# main.net
KiCad netlist of a schematic drawn in EAGLE
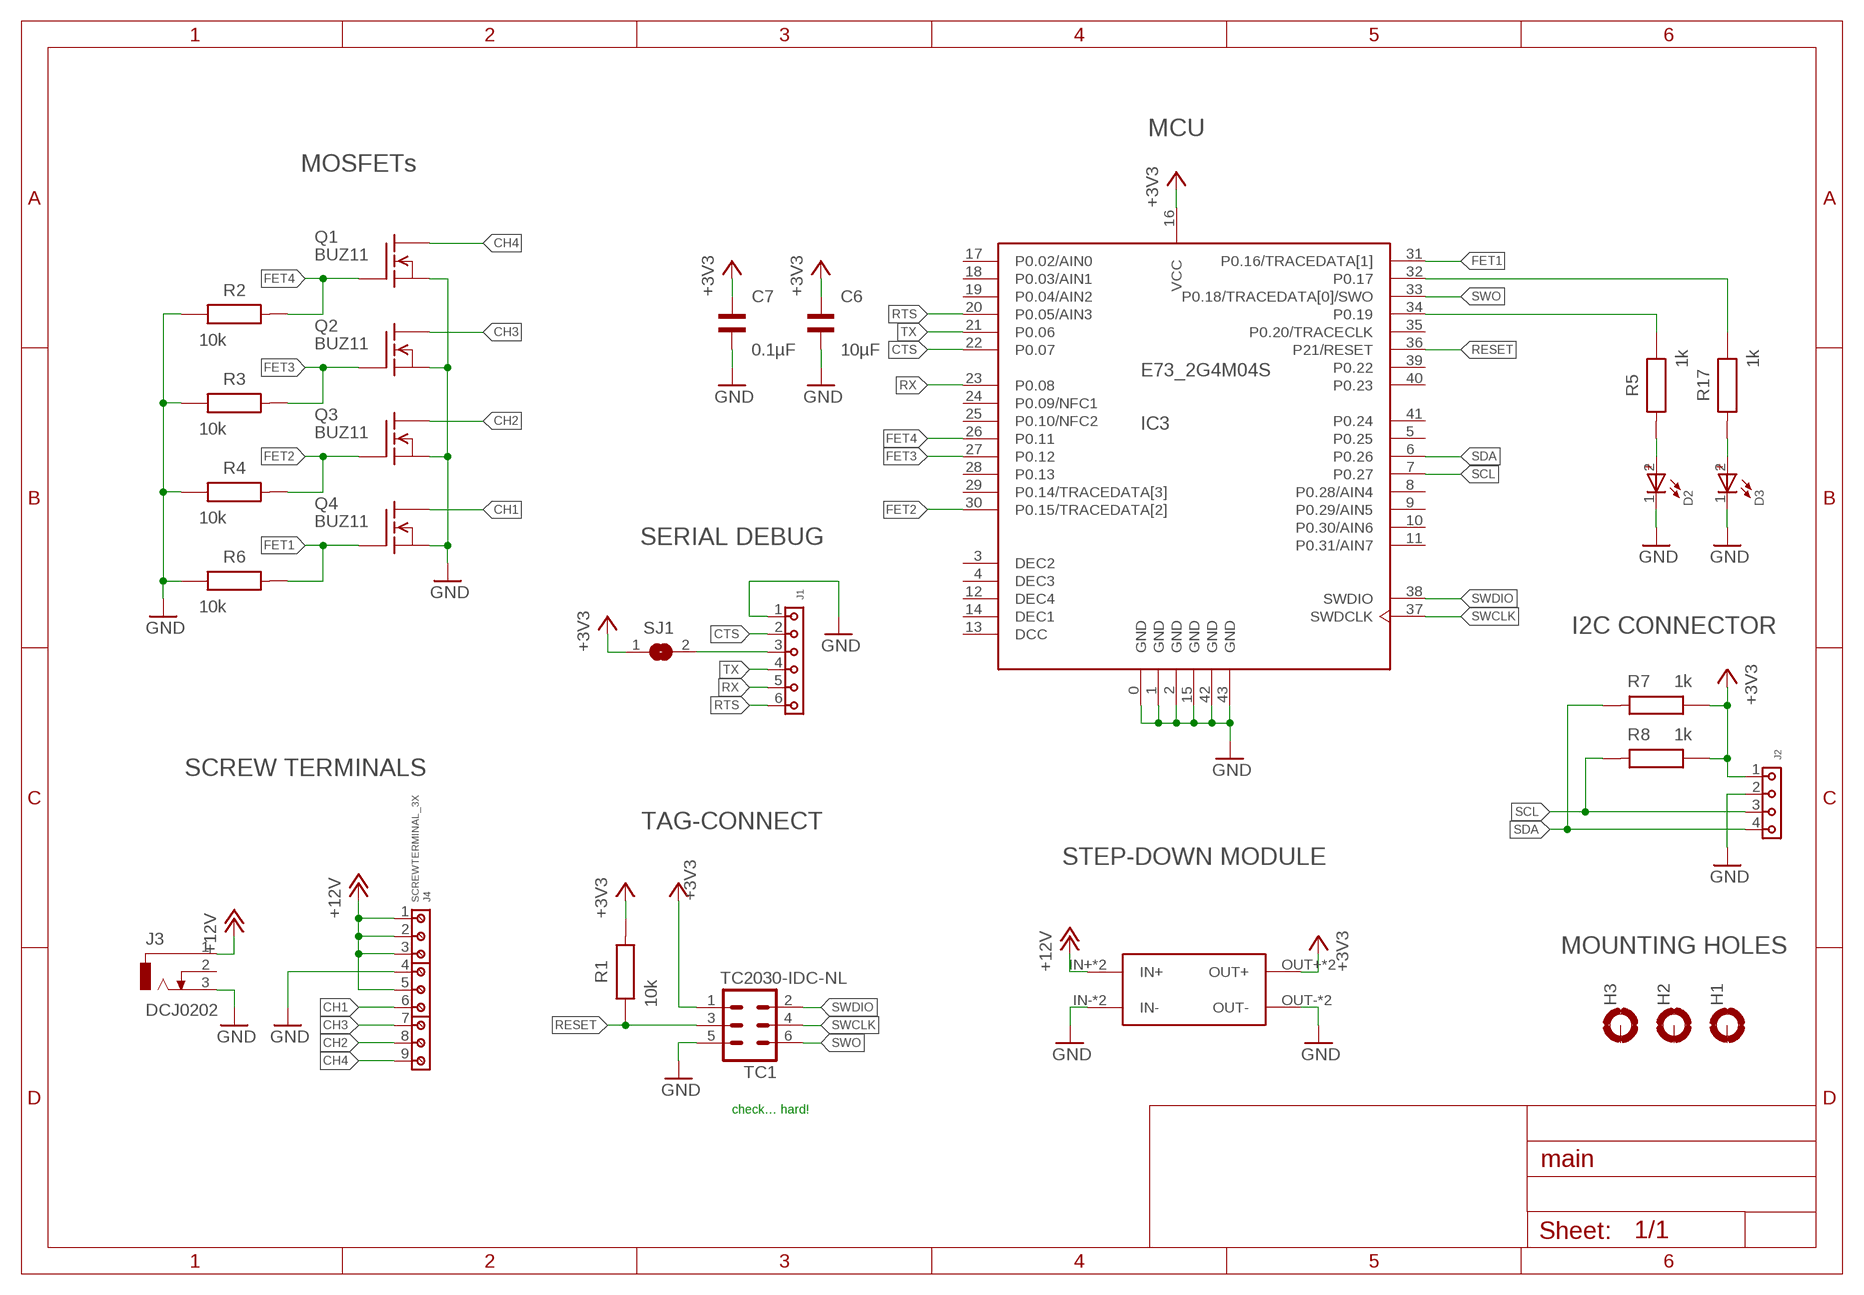
[diagram p0: schematic, sheet 1]

(export (version "E")
  (design (tool "Eeschema 10.0.6"))
  (components
    (comp (ref "C6")
      (value "10µF")
      (footprint "eagle-import:WCAP-CSGP_0603_REFLOW")
      (libsource (lib "eagle-import") (part "WCAP-CSGP_0603_REFLOW_885012206046"))
    )
    (comp (ref "C7")
      (value "0.1µF")
      (footprint "eagle-import:WCAP-CSGP_0603_REFLOW")
      (libsource (lib "eagle-import") (part "WCAP-CSGP_0603_REFLOW_885012206046"))
    )
    (comp (ref "D2")
      (value "WL-SMCW_0603_150060BS75000")
      (footprint "eagle-import:WL-SMCW_0603")
      (libsource (lib "eagle-import") (part "WL-SMCW_0603_150060BS75000"))
    )
    (comp (ref "D3")
      (value "WL-SMCW_0603_150060BS75000")
      (footprint "eagle-import:WL-SMCW_0603")
      (libsource (lib "eagle-import") (part "WL-SMCW_0603_150060BS75000"))
    )
    (comp (ref "H1")
      (value "MOUNT-PAD-ROUND3.2")
      (footprint "eagle-import:3,2-PAD")
      (libsource (lib "eagle-import") (part "MOUNT-PAD-ROUND3.2"))
    )
    (comp (ref "H2")
      (value "MOUNT-PAD-ROUND3.2")
      (footprint "eagle-import:3,2-PAD")
      (libsource (lib "eagle-import") (part "MOUNT-PAD-ROUND3.2"))
    )
    (comp (ref "H3")
      (value "MOUNT-PAD-ROUND3.2")
      (footprint "eagle-import:3,2-PAD")
      (libsource (lib "eagle-import") (part "MOUNT-PAD-ROUND3.2"))
    )
    (comp (ref "IC3")
      (value "E73_2G4M04S")
      (footprint "eagle-import:E73_2G4M04S")
      (libsource (lib "eagle-import") (part "E73_2G4M04S"))
    )
    (comp (ref "J1")
      (value "6130XX11821_61300611821")
      (footprint "eagle-import:61300611821")
      (libsource (lib "eagle-import") (part "6130XX11821_61300611821"))
    )
    (comp (ref "J2")
      (value "6130XX11821_61300411821")
      (footprint "eagle-import:61300411821")
      (libsource (lib "eagle-import") (part "6130XX11821_61300411821"))
    )
    (comp (ref "J3")
      (value "DCJ0202")
      (footprint "eagle-import:DCJ0202")
      (libsource (lib "eagle-import") (part "DCJ0202"))
    )
    (comp (ref "J4")
      (value "SCREWTERMINAL_3X")
      (footprint "eagle-import:691102710003")
      (libsource (lib "eagle-import") (part "SCREWTERMINAL_3X"))
    )
    (comp (ref "Q1")
      (value "BUZ11")
      (footprint "eagle-import:TO220")
      (libsource (lib "eagle-import") (part "BUZ11"))
    )
    (comp (ref "Q2")
      (value "BUZ11")
      (footprint "eagle-import:TO220")
      (libsource (lib "eagle-import") (part "BUZ11"))
    )
    (comp (ref "Q3")
      (value "BUZ11")
      (footprint "eagle-import:TO220")
      (libsource (lib "eagle-import") (part "BUZ11"))
    )
    (comp (ref "Q4")
      (value "BUZ11")
      (footprint "eagle-import:TO220")
      (libsource (lib "eagle-import") (part "BUZ11"))
    )
    (comp (ref "R1")
      (value "10k")
      (footprint "eagle-import:WRIS-PSMB_0603_1.6X0.8X0.35X0.6(LXWXHXPW)")
      (libsource (lib "eagle-import") (part "WRIS-PSMB_0603_1.6X0.8X0.35X0.6_580060716001"))
    )
    (comp (ref "R2")
      (value "10k")
      (footprint "eagle-import:WRIS-PSMB_0603_1.6X0.8X0.35X0.6(LXWXHXPW)")
      (libsource (lib "eagle-import") (part "WRIS-PSMB_0603_1.6X0.8X0.35X0.6_580060716001"))
    )
    (comp (ref "R3")
      (value "10k")
      (footprint "eagle-import:WRIS-PSMB_0603_1.6X0.8X0.35X0.6(LXWXHXPW)")
      (libsource (lib "eagle-import") (part "WRIS-PSMB_0603_1.6X0.8X0.35X0.6_580060716001"))
    )
    (comp (ref "R4")
      (value "10k")
      (footprint "eagle-import:WRIS-PSMB_0603_1.6X0.8X0.35X0.6(LXWXHXPW)")
      (libsource (lib "eagle-import") (part "WRIS-PSMB_0603_1.6X0.8X0.35X0.6_580060716001"))
    )
    (comp (ref "R5")
      (value "1k")
      (footprint "eagle-import:WRIS-PSMB_0603_1.6X0.8X0.35X0.6(LXWXHXPW)")
      (libsource (lib "eagle-import") (part "WRIS-PSMB_0603_1.6X0.8X0.35X0.6_580060716001"))
    )
    (comp (ref "R6")
      (value "10k")
      (footprint "eagle-import:WRIS-PSMB_0603_1.6X0.8X0.35X0.6(LXWXHXPW)")
      (libsource (lib "eagle-import") (part "WRIS-PSMB_0603_1.6X0.8X0.35X0.6_580060716001"))
    )
    (comp (ref "R7")
      (value "1k")
      (footprint "eagle-import:WRIS-PSMB_0603_1.6X0.8X0.35X0.6(LXWXHXPW)")
      (libsource (lib "eagle-import") (part "WRIS-PSMB_0603_1.6X0.8X0.35X0.6_580060716001"))
    )
    (comp (ref "R8")
      (value "1k")
      (footprint "eagle-import:WRIS-PSMB_0603_1.6X0.8X0.35X0.6(LXWXHXPW)")
      (libsource (lib "eagle-import") (part "WRIS-PSMB_0603_1.6X0.8X0.35X0.6_580060716001"))
    )
    (comp (ref "R17")
      (value "1k")
      (footprint "eagle-import:WRIS-PSMB_0603_1.6X0.8X0.35X0.6(LXWXHXPW)")
      (libsource (lib "eagle-import") (part "WRIS-PSMB_0603_1.6X0.8X0.35X0.6_580060716001"))
    )
    (comp (ref "SJ1") (value "SJ") (footprint "eagle-import:SJ") (libsource (lib "eagle-import") (part "SJ")))
    (comp (ref "TC1")
      (value "TC2030-IDC-NL")
      (footprint "eagle-import:TC2030-IDC-NL")
      (libsource (lib "eagle-import") (part "TC2030-IDC-NL"))
    )
    (comp (ref "U$1")
      (value "LM2596-MODULE")
      (footprint "eagle-import:LM2596-MODULE")
      (libsource (lib "eagle-import") (part "LM2596-MODULE"))
    )
  )
  (nets
    (net (code "1") (name "+3V3") (class "Default")
      (node (ref "C6") (pin "2") (pinfunction "2_2") (pintype "passive"))
      (node (ref "C7") (pin "2") (pinfunction "2_2") (pintype "passive"))
      (node (ref "IC3") (pin "16") (pinfunction "VCC_16") (pintype "passive"))
      (node (ref "J2") (pin "1") (pinfunction "1_1") (pintype "passive"))
      (node (ref "R1") (pin "2") (pinfunction "2_2") (pintype "passive"))
      (node (ref "R7") (pin "1") (pinfunction "1_1") (pintype "passive"))
      (node (ref "R8") (pin "1") (pinfunction "1_1") (pintype "passive"))
      (node (ref "SJ1") (pin "1") (pinfunction "1_1") (pintype "passive"))
      (node (ref "TC1") (pin "1") (pinfunction "1_1") (pintype "passive"))
      (node (ref "U$1") (pin "OUT+") (pinfunction "OUT+_OUT+") (pintype "bidirectional"))
      (node (ref "U$1") (pin "OUT+1") (pinfunction "OUT+_OUT+1") (pintype "bidirectional"))
    )
    (net (code "2") (name "+12V") (class "Default")
      (node (ref "J3") (pin "1") (pinfunction "1_1") (pintype "passive"))
      (node (ref "J4") (pin "1") (pinfunction "1_1") (pintype "passive"))
      (node (ref "J4") (pin "2") (pinfunction "2_2") (pintype "passive"))
      (node (ref "J4") (pin "3") (pinfunction "3_3") (pintype "passive"))
      (node (ref "J4") (pin "5") (pinfunction "5_5") (pintype "passive"))
      (node (ref "U$1") (pin "IN+") (pinfunction "IN+_IN+") (pintype "bidirectional"))
      (node (ref "U$1") (pin "IN+1") (pinfunction "IN+_IN+1") (pintype "bidirectional"))
    )
    (net (code "3") (name "/DCC") (class "Default")
      (node (ref "IC3") (pin "13") (pinfunction "DCC_13") (pintype "power_in"))
    )
    (net (code "4") (name "/DEC1") (class "Default")
      (node (ref "IC3") (pin "14") (pinfunction "DEC1_14") (pintype "power_in"))
    )
    (net (code "5") (name "/DEC2") (class "Default")
      (node (ref "IC3") (pin "3") (pinfunction "DEC2_3") (pintype "power_in"))
    )
    (net (code "6") (name "/DEC3") (class "Default")
      (node (ref "IC3") (pin "4") (pinfunction "DEC3_4") (pintype "power_in"))
    )
    (net (code "7") (name "/DEC4") (class "Default")
      (node (ref "IC3") (pin "12") (pinfunction "DEC4_12") (pintype "power_in"))
    )
    (net (code "8") (name "CH1") (class "Default")
      (node (ref "J4") (pin "6") (pinfunction "6_6") (pintype "passive"))
      (node (ref "Q4") (pin "2") (pinfunction "D_2") (pintype "passive"))
    )
    (net (code "9") (name "CH2") (class "Default")
      (node (ref "J4") (pin "8") (pinfunction "8_8") (pintype "passive"))
      (node (ref "Q3") (pin "2") (pinfunction "D_2") (pintype "passive"))
    )
    (net (code "10") (name "CH3") (class "Default")
      (node (ref "J4") (pin "7") (pinfunction "7_7") (pintype "passive"))
      (node (ref "Q2") (pin "2") (pinfunction "D_2") (pintype "passive"))
    )
    (net (code "11") (name "CH4") (class "Default")
      (node (ref "J4") (pin "9") (pinfunction "9_9") (pintype "passive"))
      (node (ref "Q1") (pin "2") (pinfunction "D_2") (pintype "passive"))
    )
    (net (code "12") (name "CTS") (class "Default")
      (node (ref "IC3") (pin "22") (pinfunction "P0.07_22") (pintype "bidirectional"))
      (node (ref "J1") (pin "2") (pinfunction "2_2") (pintype "passive"))
    )
    (net (code "13") (name "FET1") (class "Default")
      (node (ref "IC3") (pin "31") (pinfunction "P0.16/TRACEDATA[1]_31") (pintype "bidirectional"))
      (node (ref "Q4") (pin "1") (pinfunction "G_1") (pintype "passive"))
      (node (ref "R6") (pin "2") (pinfunction "2_2") (pintype "passive"))
    )
    (net (code "14") (name "FET2") (class "Default")
      (node (ref "IC3") (pin "30") (pinfunction "P0.15/TRACEDATA[2]_30") (pintype "bidirectional"))
      (node (ref "Q3") (pin "1") (pinfunction "G_1") (pintype "passive"))
      (node (ref "R4") (pin "2") (pinfunction "2_2") (pintype "passive"))
    )
    (net (code "15") (name "FET3") (class "Default")
      (node (ref "IC3") (pin "27") (pinfunction "P0.12_27") (pintype "bidirectional"))
      (node (ref "Q2") (pin "1") (pinfunction "G_1") (pintype "passive"))
      (node (ref "R3") (pin "2") (pinfunction "2_2") (pintype "passive"))
    )
    (net (code "16") (name "FET4") (class "Default")
      (node (ref "IC3") (pin "26") (pinfunction "P0.11_26") (pintype "bidirectional"))
      (node (ref "Q1") (pin "1") (pinfunction "G_1") (pintype "passive"))
      (node (ref "R2") (pin "2") (pinfunction "2_2") (pintype "passive"))
    )
    (net (code "17") (name "GND") (class "Default")
      (node (ref "C6") (pin "1") (pinfunction "1_1") (pintype "passive"))
      (node (ref "C7") (pin "1") (pinfunction "1_1") (pintype "passive"))
      (node (ref "D2") (pin "1") (pinfunction "-_1") (pintype "passive"))
      (node (ref "D3") (pin "1") (pinfunction "-_1") (pintype "passive"))
      (node (ref "IC3") (pin "0") (pinfunction "GND_0") (pintype "bidirectional"))
      (node (ref "IC3") (pin "1") (pinfunction "GND_1") (pintype "bidirectional"))
      (node (ref "IC3") (pin "15") (pinfunction "GND_15") (pintype "bidirectional"))
      (node (ref "IC3") (pin "2") (pinfunction "GND_2") (pintype "bidirectional"))
      (node (ref "IC3") (pin "42") (pinfunction "GND_42") (pintype "bidirectional"))
      (node (ref "IC3") (pin "43") (pinfunction "GND_43") (pintype "bidirectional"))
      (node (ref "J1") (pin "1") (pinfunction "1_1") (pintype "passive"))
      (node (ref "J2") (pin "2") (pinfunction "2_2") (pintype "passive"))
      (node (ref "J3") (pin "3") (pinfunction "3_3") (pintype "passive"))
      (node (ref "J4") (pin "4") (pinfunction "4_4") (pintype "passive"))
      (node (ref "Q1") (pin "3") (pinfunction "S_3") (pintype "passive"))
      (node (ref "Q2") (pin "3") (pinfunction "S_3") (pintype "passive"))
      (node (ref "Q3") (pin "3") (pinfunction "S_3") (pintype "passive"))
      (node (ref "Q4") (pin "3") (pinfunction "S_3") (pintype "passive"))
      (node (ref "R2") (pin "1") (pinfunction "1_1") (pintype "passive"))
      (node (ref "R3") (pin "1") (pinfunction "1_1") (pintype "passive"))
      (node (ref "R4") (pin "1") (pinfunction "1_1") (pintype "passive"))
      (node (ref "R6") (pin "1") (pinfunction "1_1") (pintype "passive"))
      (node (ref "TC1") (pin "5") (pinfunction "5_5") (pintype "passive"))
      (node (ref "U$1") (pin "IN-") (pinfunction "IN-_IN-") (pintype "bidirectional"))
      (node (ref "U$1") (pin "IN-1") (pinfunction "IN-_IN-1") (pintype "bidirectional"))
      (node (ref "U$1") (pin "OUT-") (pinfunction "OUT-_OUT-") (pintype "bidirectional"))
      (node (ref "U$1") (pin "OUT-1") (pinfunction "OUT-_OUT-1") (pintype "bidirectional"))
    )
    (net (code "18") (name "Net-(D2-+)") (class "Default")
      (node (ref "D2") (pin "2") (pinfunction "+_2") (pintype "passive"))
      (node (ref "R5") (pin "2") (pinfunction "2_2") (pintype "passive"))
    )
    (net (code "19") (name "Net-(D3-+)") (class "Default")
      (node (ref "D3") (pin "2") (pinfunction "+_2") (pintype "passive"))
      (node (ref "R17") (pin "2") (pinfunction "2_2") (pintype "passive"))
    )
    (net (code "20") (name "Net-(IC3-P0.17)") (class "Default")
      (node (ref "IC3") (pin "32") (pinfunction "P0.17_32") (pintype "bidirectional"))
      (node (ref "R17") (pin "1") (pinfunction "1_1") (pintype "passive"))
    )
    (net (code "21") (name "Net-(IC3-P0.19)") (class "Default")
      (node (ref "IC3") (pin "34") (pinfunction "P0.19_34") (pintype "bidirectional"))
      (node (ref "R5") (pin "1") (pinfunction "1_1") (pintype "passive"))
    )
    (net (code "22") (name "Net-(J1-Pad3)") (class "Default")
      (node (ref "J1") (pin "3") (pinfunction "3_3") (pintype "passive"))
      (node (ref "SJ1") (pin "2") (pinfunction "2_2") (pintype "passive"))
    )
    (net (code "23") (name "RESET") (class "Default")
      (node (ref "IC3") (pin "36") (pinfunction "P21/RESET_36") (pintype "bidirectional"))
      (node (ref "R1") (pin "1") (pinfunction "1_1") (pintype "passive"))
      (node (ref "TC1") (pin "3") (pinfunction "3_3") (pintype "passive"))
    )
    (net (code "24") (name "RTS") (class "Default")
      (node (ref "IC3") (pin "20") (pinfunction "P0.05/AIN3_20") (pintype "bidirectional"))
      (node (ref "J1") (pin "6") (pinfunction "6_6") (pintype "passive"))
    )
    (net (code "25") (name "RX") (class "Default")
      (node (ref "IC3") (pin "23") (pinfunction "P0.08_23") (pintype "bidirectional"))
      (node (ref "J1") (pin "5") (pinfunction "5_5") (pintype "passive"))
    )
    (net (code "26") (name "SCL") (class "Default")
      (node (ref "IC3") (pin "7") (pinfunction "P0.27_7") (pintype "bidirectional"))
      (node (ref "J2") (pin "3") (pinfunction "3_3") (pintype "passive"))
      (node (ref "R8") (pin "2") (pinfunction "2_2") (pintype "passive"))
    )
    (net (code "27") (name "SDA") (class "Default")
      (node (ref "IC3") (pin "6") (pinfunction "P0.26_6") (pintype "bidirectional"))
      (node (ref "J2") (pin "4") (pinfunction "4_4") (pintype "passive"))
      (node (ref "R7") (pin "2") (pinfunction "2_2") (pintype "passive"))
    )
    (net (code "28") (name "SWCLK") (class "Default")
      (node (ref "IC3") (pin "37") (pinfunction "SWDCLK_37") (pintype "input"))
      (node (ref "TC1") (pin "4") (pinfunction "4_4") (pintype "passive"))
    )
    (net (code "29") (name "SWDIO") (class "Default")
      (node (ref "IC3") (pin "38") (pinfunction "SWDIO_38") (pintype "bidirectional"))
      (node (ref "TC1") (pin "2") (pinfunction "2_2") (pintype "passive"))
    )
    (net (code "30") (name "SWO") (class "Default")
      (node (ref "IC3") (pin "33") (pinfunction "P0.18/TRACEDATA[0]/SWO_33") (pintype "bidirectional"))
      (node (ref "TC1") (pin "6") (pinfunction "6_6") (pintype "passive"))
    )
    (net (code "31") (name "TX") (class "Default")
      (node (ref "IC3") (pin "21") (pinfunction "P0.06_21") (pintype "bidirectional"))
      (node (ref "J1") (pin "4") (pinfunction "4_4") (pintype "passive"))
    )
    (net (code "32") (name "unconnected-(H1-MOUNT-PadB3,2)") (class "Default")
      (node (ref "H1") (pin "B3,2") (pinfunction "MOUNT_B3,2") (pintype "passive"))
    )
    (net (code "33") (name "unconnected-(H2-MOUNT-PadB3,2)") (class "Default")
      (node (ref "H2") (pin "B3,2") (pinfunction "MOUNT_B3,2") (pintype "passive"))
    )
    (net (code "34") (name "unconnected-(H3-MOUNT-PadB3,2)") (class "Default")
      (node (ref "H3") (pin "B3,2") (pinfunction "MOUNT_B3,2") (pintype "passive"))
    )
    (net (code "35") (name "unconnected-(IC3-P0.02{slash}AIN0-Pad17)") (class "Default")
      (node (ref "IC3") (pin "17") (pinfunction "P0.02/AIN0_17") (pintype "bidirectional"))
    )
    (net (code "36") (name "unconnected-(IC3-P0.03{slash}AIN1-Pad18)") (class "Default")
      (node (ref "IC3") (pin "18") (pinfunction "P0.03/AIN1_18") (pintype "bidirectional"))
    )
    (net (code "37") (name "unconnected-(IC3-P0.04{slash}AIN2-Pad19)") (class "Default")
      (node (ref "IC3") (pin "19") (pinfunction "P0.04/AIN2_19") (pintype "bidirectional"))
    )
    (net (code "38") (name "unconnected-(IC3-P0.09{slash}NFC1-Pad24)") (class "Default")
      (node (ref "IC3") (pin "24") (pinfunction "P0.09/NFC1_24") (pintype "bidirectional"))
    )
    (net (code "39") (name "unconnected-(IC3-P0.10{slash}NFC2-Pad25)") (class "Default")
      (node (ref "IC3") (pin "25") (pinfunction "P0.10/NFC2_25") (pintype "bidirectional"))
    )
    (net (code "40") (name "unconnected-(IC3-P0.13-Pad28)") (class "Default")
      (node (ref "IC3") (pin "28") (pinfunction "P0.13_28") (pintype "bidirectional"))
    )
    (net (code "41") (name "unconnected-(IC3-P0.14{slash}TRACEDATA[3]-Pad29)") (class "Default")
      (node (ref "IC3") (pin "29") (pinfunction "P0.14/TRACEDATA[3]_29") (pintype "bidirectional"))
    )
    (net (code "42") (name "unconnected-(IC3-P0.20{slash}TRACECLK-Pad35)") (class "Default")
      (node (ref "IC3") (pin "35") (pinfunction "P0.20/TRACECLK_35") (pintype "bidirectional"))
    )
    (net (code "43") (name "unconnected-(IC3-P0.22-Pad39)") (class "Default")
      (node (ref "IC3") (pin "39") (pinfunction "P0.22_39") (pintype "bidirectional"))
    )
    (net (code "44") (name "unconnected-(IC3-P0.23-Pad40)") (class "Default")
      (node (ref "IC3") (pin "40") (pinfunction "P0.23_40") (pintype "bidirectional"))
    )
    (net (code "45") (name "unconnected-(IC3-P0.24-Pad41)") (class "Default")
      (node (ref "IC3") (pin "41") (pinfunction "P0.24_41") (pintype "bidirectional"))
    )
    (net (code "46") (name "unconnected-(IC3-P0.25-Pad5)") (class "Default")
      (node (ref "IC3") (pin "5") (pinfunction "P0.25_5") (pintype "bidirectional"))
    )
    (net (code "47") (name "unconnected-(IC3-P0.28{slash}AIN4-Pad8)") (class "Default")
      (node (ref "IC3") (pin "8") (pinfunction "P0.28/AIN4_8") (pintype "bidirectional"))
    )
    (net (code "48") (name "unconnected-(IC3-P0.29{slash}AIN5-Pad9)") (class "Default")
      (node (ref "IC3") (pin "9") (pinfunction "P0.29/AIN5_9") (pintype "bidirectional"))
    )
    (net (code "49") (name "unconnected-(IC3-P0.30{slash}AIN6-Pad10)") (class "Default")
      (node (ref "IC3") (pin "10") (pinfunction "P0.30/AIN6_10") (pintype "bidirectional"))
    )
    (net (code "50") (name "unconnected-(IC3-P0.31{slash}AIN7-Pad11)") (class "Default")
      (node (ref "IC3") (pin "11") (pinfunction "P0.31/AIN7_11") (pintype "bidirectional"))
    )
    (net (code "51") (name "unconnected-(J3-Pad2)") (class "Default")
      (node (ref "J3") (pin "2") (pinfunction "2_2") (pintype "passive"))
    )
  )
)
